# 2_MCU.net
KiCad netlist of a schematic drawn in Altium Designer
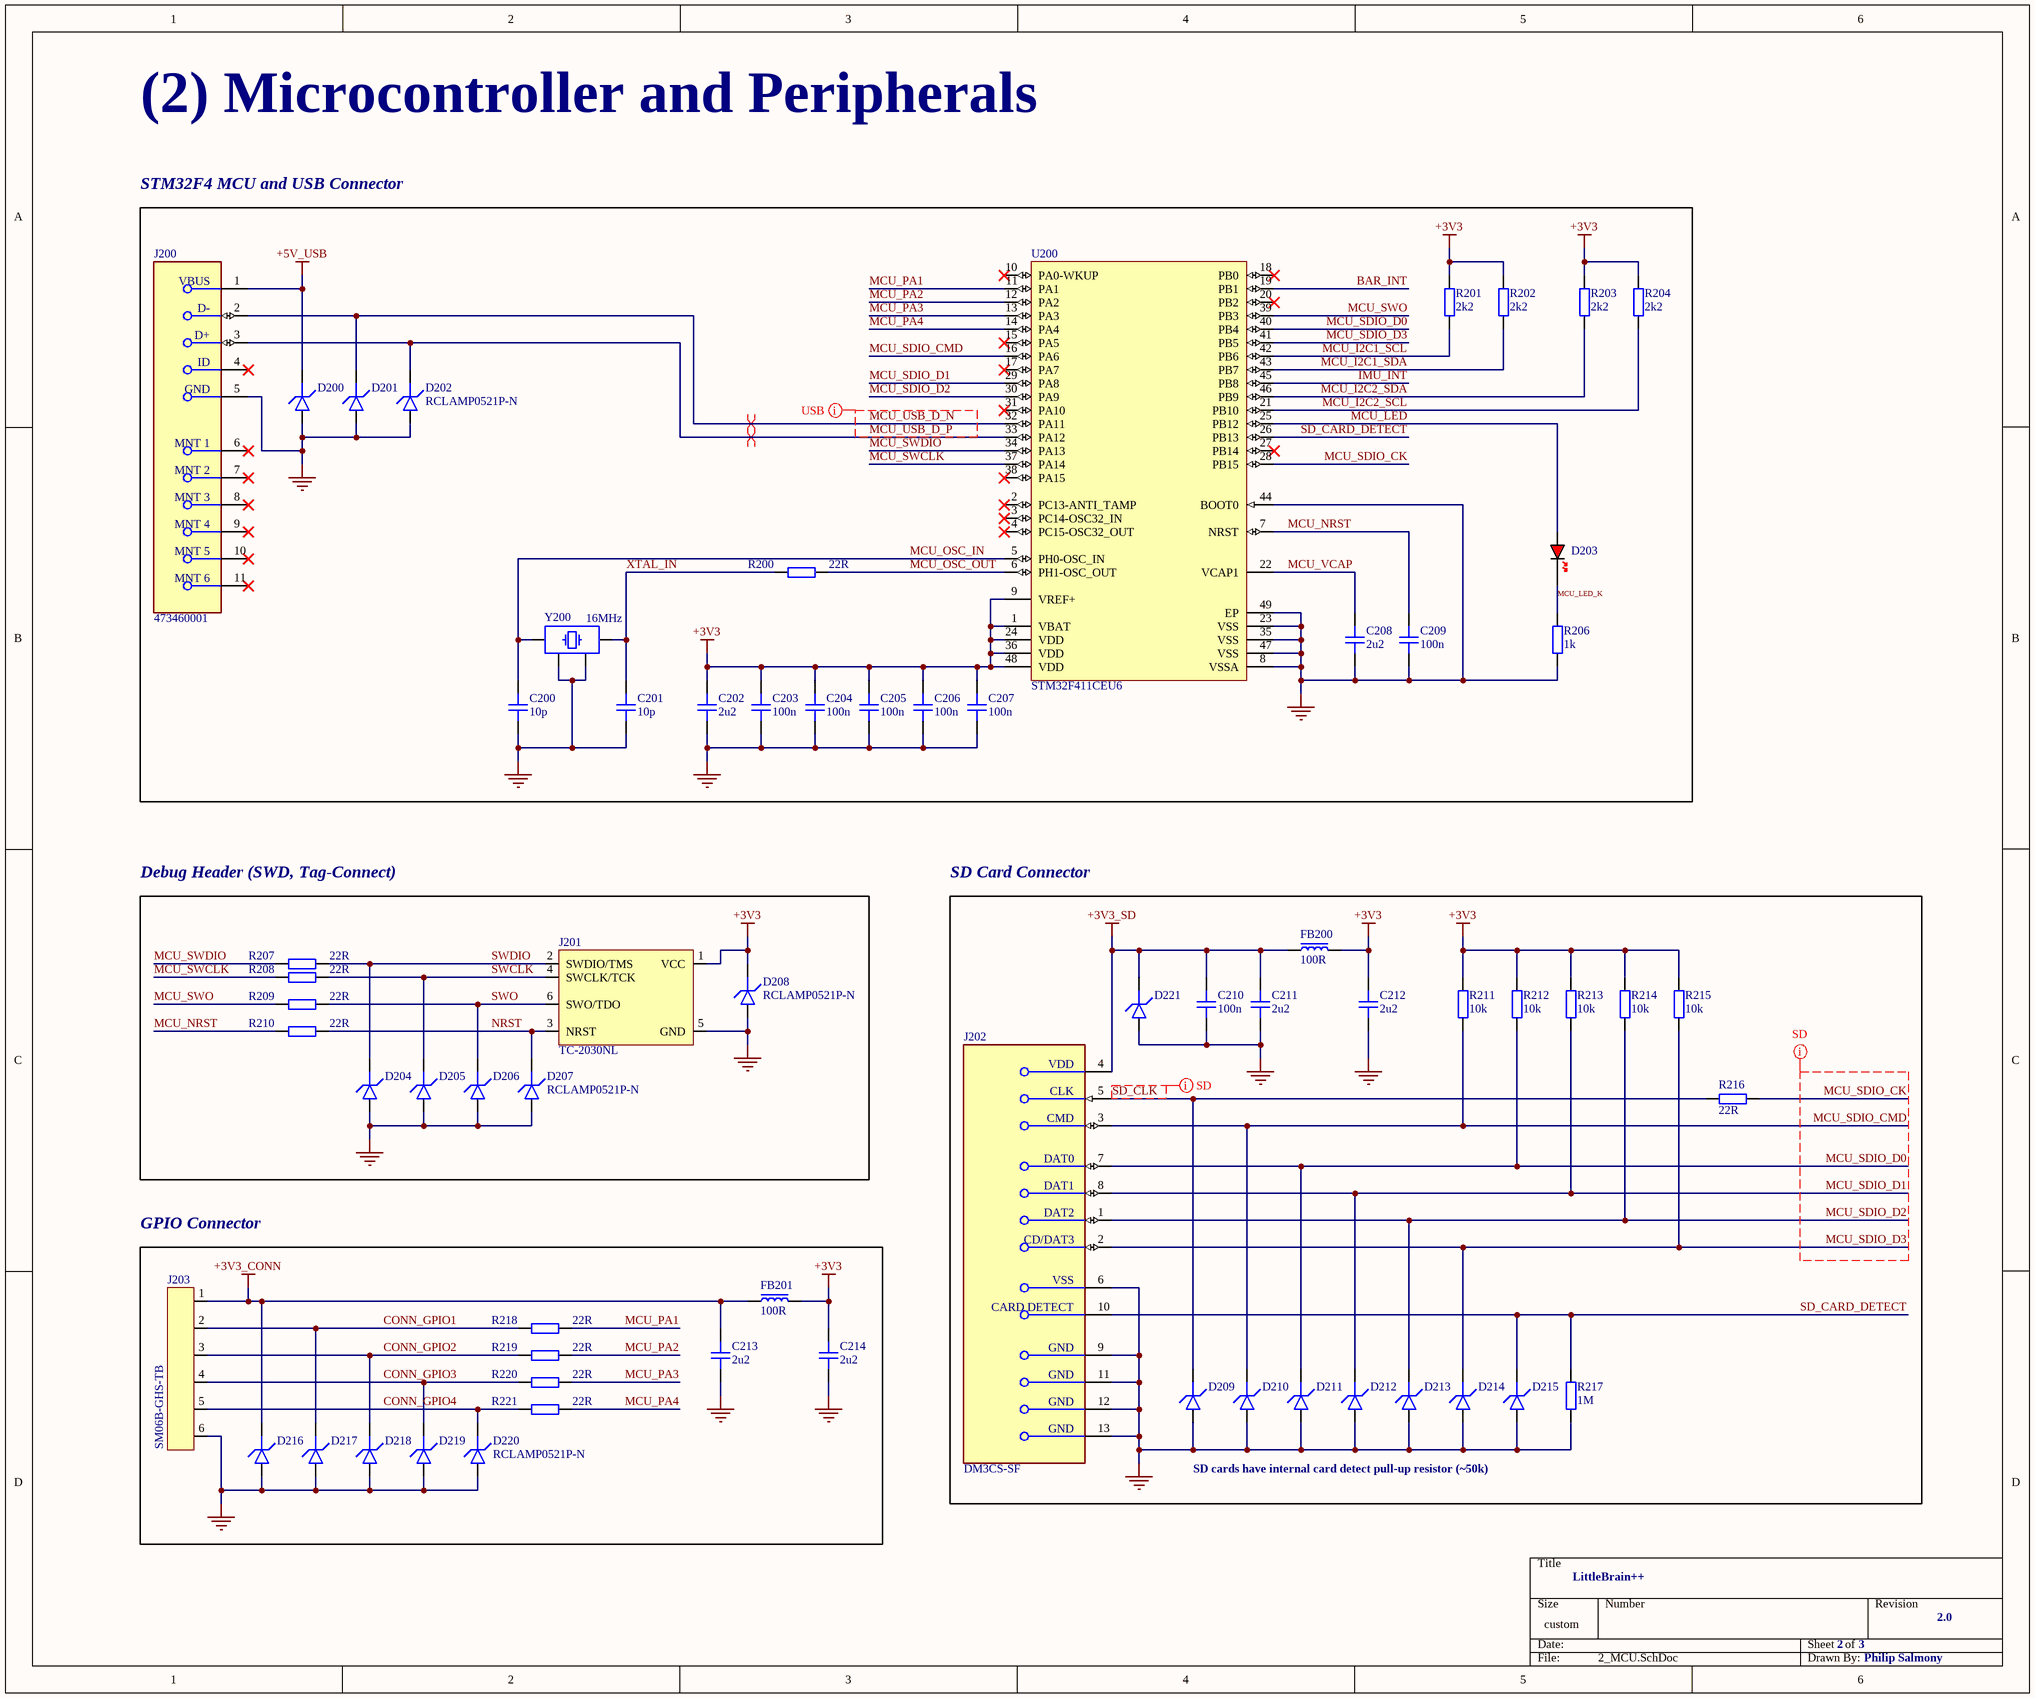
[diagram p0: 2_MCU.SchDoc]

(export (version "E")
  (design (tool "Eeschema 10.0.6"))
  (components
    (comp (ref "C200")
      (value "10p")
      (footprint "CAP_0402")
      (description "Capacitor SMD 0402 16V")
      (libsource (lib "Schematic-Lib-PhilsLab") (part "CAP_0402_16V"))
    )
    (comp (ref "C201")
      (value "10p")
      (footprint "CAP_0402")
      (description "Capacitor SMD 0402 16V")
      (libsource (lib "Schematic-Lib-PhilsLab") (part "CAP_0402_16V"))
    )
    (comp (ref "C202")
      (value "2u2")
      (footprint "CAP_0603")
      (description "Capacitor SMD 0603 16V")
      (libsource (lib "Schematic-Lib-PhilsLab") (part "CAP_0603_16V"))
    )
    (comp (ref "C203")
      (value "100n")
      (footprint "CAP_0402")
      (description "Capacitor SMD 0402 16V")
      (libsource (lib "Schematic-Lib-PhilsLab") (part "CAP_0402_16V"))
    )
    (comp (ref "C204")
      (value "100n")
      (footprint "CAP_0402")
      (description "Capacitor SMD 0402 16V")
      (libsource (lib "Schematic-Lib-PhilsLab") (part "CAP_0402_16V"))
    )
    (comp (ref "C205")
      (value "100n")
      (footprint "CAP_0402")
      (description "Capacitor SMD 0402 16V")
      (libsource (lib "Schematic-Lib-PhilsLab") (part "CAP_0402_16V"))
    )
    (comp (ref "C206")
      (value "100n")
      (footprint "CAP_0402")
      (description "Capacitor SMD 0402 16V")
      (libsource (lib "Schematic-Lib-PhilsLab") (part "CAP_0402_16V"))
    )
    (comp (ref "C207")
      (value "100n")
      (footprint "CAP_0402")
      (description "Capacitor SMD 0402 16V")
      (libsource (lib "Schematic-Lib-PhilsLab") (part "CAP_0402_16V"))
    )
    (comp (ref "C208")
      (value "2u2")
      (footprint "CAP_0603")
      (description "Capacitor SMD 0603 16V")
      (libsource (lib "Schematic-Lib-PhilsLab") (part "CAP_0603_16V"))
    )
    (comp (ref "C209")
      (value "100n")
      (footprint "CAP_0402")
      (description "Capacitor SMD 0402 16V")
      (libsource (lib "Schematic-Lib-PhilsLab") (part "CAP_0402_16V"))
    )
    (comp (ref "C210")
      (value "100n")
      (footprint "CAP_0402")
      (description "Capacitor SMD 0402 16V")
      (libsource (lib "Schematic-Lib-PhilsLab") (part "CAP_0402_16V"))
    )
    (comp (ref "C211")
      (value "2u2")
      (footprint "CAP_0603")
      (description "Capacitor SMD 0603 16V")
      (libsource (lib "Schematic-Lib-PhilsLab") (part "CAP_0603_16V"))
    )
    (comp (ref "C212")
      (value "2u2")
      (footprint "CAP_0603")
      (description "Capacitor SMD 0603 16V")
      (libsource (lib "Schematic-Lib-PhilsLab") (part "CAP_0603_16V"))
    )
    (comp (ref "C213")
      (value "2u2")
      (footprint "CAP_0603")
      (description "Capacitor SMD 0603 16V")
      (libsource (lib "Schematic-Lib-PhilsLab") (part "CAP_0603_16V"))
    )
    (comp (ref "C214")
      (value "2u2")
      (footprint "CAP_0603")
      (description "Capacitor SMD 0603 16V")
      (libsource (lib "Schematic-Lib-PhilsLab") (part "CAP_0603_16V"))
    )
    (comp (ref "D200")
      (value "RCLAMP0521P-N")
      (footprint "D_0402")
      (description "Diode TVS / ESD 0402")
      (libsource (lib "Schematic-Lib-PhilsLab") (part "D_TVS_0402"))
    )
    (comp (ref "D201")
      (value "RCLAMP0521P-N")
      (footprint "D_0402")
      (description "Diode TVS / ESD 0402")
      (libsource (lib "Schematic-Lib-PhilsLab") (part "D_TVS_0402"))
    )
    (comp (ref "D202")
      (value "RCLAMP0521P-N")
      (footprint "D_0402")
      (description "Diode TVS / ESD 0402")
      (libsource (lib "Schematic-Lib-PhilsLab") (part "D_TVS_0402"))
    )
    (comp (ref "D203")
      (value "RED")
      (footprint "LED_0402_RED")
      (description "LED 0402 RED SMD")
      (libsource (lib "Schematic-Lib-PhilsLab") (part "LED_0402_RED"))
    )
    (comp (ref "D204")
      (value "RCLAMP0521P-N")
      (footprint "D_0402")
      (description "Diode TVS / ESD 0402")
      (libsource (lib "Schematic-Lib-PhilsLab") (part "D_TVS_0402"))
    )
    (comp (ref "D205")
      (value "RCLAMP0521P-N")
      (footprint "D_0402")
      (description "Diode TVS / ESD 0402")
      (libsource (lib "Schematic-Lib-PhilsLab") (part "D_TVS_0402"))
    )
    (comp (ref "D206")
      (value "RCLAMP0521P-N")
      (footprint "D_0402")
      (description "Diode TVS / ESD 0402")
      (libsource (lib "Schematic-Lib-PhilsLab") (part "D_TVS_0402"))
    )
    (comp (ref "D207")
      (value "RCLAMP0521P-N")
      (footprint "D_0402")
      (description "Diode TVS / ESD 0402")
      (libsource (lib "Schematic-Lib-PhilsLab") (part "D_TVS_0402"))
    )
    (comp (ref "D208")
      (value "RCLAMP0521P-N")
      (footprint "D_0402")
      (description "Diode TVS / ESD 0402")
      (libsource (lib "Schematic-Lib-PhilsLab") (part "D_TVS_0402"))
    )
    (comp (ref "D209")
      (value "RCLAMP0521P-N")
      (footprint "D_0402")
      (description "Diode TVS / ESD 0402")
      (libsource (lib "Schematic-Lib-PhilsLab") (part "D_TVS_0402"))
    )
    (comp (ref "D210")
      (value "RCLAMP0521P-N")
      (footprint "D_0402")
      (description "Diode TVS / ESD 0402")
      (libsource (lib "Schematic-Lib-PhilsLab") (part "D_TVS_0402"))
    )
    (comp (ref "D211")
      (value "RCLAMP0521P-N")
      (footprint "D_0402")
      (description "Diode TVS / ESD 0402")
      (libsource (lib "Schematic-Lib-PhilsLab") (part "D_TVS_0402"))
    )
    (comp (ref "D212")
      (value "RCLAMP0521P-N")
      (footprint "D_0402")
      (description "Diode TVS / ESD 0402")
      (libsource (lib "Schematic-Lib-PhilsLab") (part "D_TVS_0402"))
    )
    (comp (ref "D213")
      (value "RCLAMP0521P-N")
      (footprint "D_0402")
      (description "Diode TVS / ESD 0402")
      (libsource (lib "Schematic-Lib-PhilsLab") (part "D_TVS_0402"))
    )
    (comp (ref "D214")
      (value "RCLAMP0521P-N")
      (footprint "D_0402")
      (description "Diode TVS / ESD 0402")
      (libsource (lib "Schematic-Lib-PhilsLab") (part "D_TVS_0402"))
    )
    (comp (ref "D215")
      (value "RCLAMP0521P-N")
      (footprint "D_0402")
      (description "Diode TVS / ESD 0402")
      (libsource (lib "Schematic-Lib-PhilsLab") (part "D_TVS_0402"))
    )
    (comp (ref "D216")
      (value "RCLAMP0521P-N")
      (footprint "D_0402")
      (description "Diode TVS / ESD 0402")
      (libsource (lib "Schematic-Lib-PhilsLab") (part "D_TVS_0402"))
    )
    (comp (ref "D217")
      (value "RCLAMP0521P-N")
      (footprint "D_0402")
      (description "Diode TVS / ESD 0402")
      (libsource (lib "Schematic-Lib-PhilsLab") (part "D_TVS_0402"))
    )
    (comp (ref "D218")
      (value "RCLAMP0521P-N")
      (footprint "D_0402")
      (description "Diode TVS / ESD 0402")
      (libsource (lib "Schematic-Lib-PhilsLab") (part "D_TVS_0402"))
    )
    (comp (ref "D219")
      (value "RCLAMP0521P-N")
      (footprint "D_0402")
      (description "Diode TVS / ESD 0402")
      (libsource (lib "Schematic-Lib-PhilsLab") (part "D_TVS_0402"))
    )
    (comp (ref "D220")
      (value "RCLAMP0521P-N")
      (footprint "D_0402")
      (description "Diode TVS / ESD 0402")
      (libsource (lib "Schematic-Lib-PhilsLab") (part "D_TVS_0402"))
    )
    (comp (ref "D221")
      (value "RCLAMP0521P-N")
      (footprint "D_0402")
      (description "Diode TVS / ESD 0402")
      (libsource (lib "Schematic-Lib-PhilsLab") (part "D_TVS_0402"))
    )
    (comp (ref "FB200")
      (value "100R")
      (footprint "FB_0603")
      (description "Ferrite Bead SMD 0603")
      (libsource (lib "Schematic-Lib-PhilsLab") (part "FB_0603"))
    )
    (comp (ref "FB201")
      (value "100R")
      (footprint "FB_0603")
      (description "Ferrite Bead SMD 0603")
      (libsource (lib "Schematic-Lib-PhilsLab") (part "FB_0603"))
    )
    (comp (ref "J200")
      (value "473460001")
      (footprint "FP-473460001-MFG")
      (description "CONN RCPT USB2.0 MICRO B SMD R/A")
      (fields
        (field (name "OCTOPART") "https://octopart.com/47346-0001-molex-7164928")
        (field (name "MANUFACTURER") "Molex")
      )
      (libsource (lib "Altium Content Vault") (part "53ae1f1d9b557310b43ca686e5bb76a"))
    )
    (comp (ref "J201")
      (value "TC-2030NL")
      (footprint "TC2030-NL-FP")
      (description "Tag-Connect No-Solder SWD Debug Connector (No Legs) DO NOT PLACE")
      (fields (field (name "MANUFACTURER") "Tag-Connect"))
      (libsource (lib "Schematic-Lib-PhilsLab") (part "TC2030-NL"))
    )
    (comp (ref "J202")
      (value "DM3CS-SF")
      (footprint "FP-DM3CS-SF-MFG")
      (description "CONN MICRO SD CARD HINGED TYPE")
      (libsource (lib "Altium Content Vault") (part "bac915de5305cfdd1ca301aae530106"))
    )
    (comp (ref "J203")
      (value "SM06B-GHS-TB")
      (footprint "SM06B-GHS-TB")
      (description "Header Connector 6 Position 1.25MM Pitch SMD Horizontal JST GH")
      (fields (field (name "MANUFACTURER") "JST"))
      (libsource (lib "Schematic-Lib-PhilsLab") (part "SM06B-GHS-TB"))
    )
    (comp (ref "R200")
      (value "22R")
      (footprint "RES_0402")
      (description "Resistor SMD 0402")
      (libsource (lib "Schematic-Lib-PhilsLab") (part "RES_0402"))
    )
    (comp (ref "R201")
      (value "2k2")
      (footprint "RES_0402")
      (description "Resistor SMD 0402")
      (libsource (lib "Schematic-Lib-PhilsLab") (part "RES_0402"))
    )
    (comp (ref "R202")
      (value "2k2")
      (footprint "RES_0402")
      (description "Resistor SMD 0402")
      (libsource (lib "Schematic-Lib-PhilsLab") (part "RES_0402"))
    )
    (comp (ref "R203")
      (value "2k2")
      (footprint "RES_0402")
      (description "Resistor SMD 0402")
      (libsource (lib "Schematic-Lib-PhilsLab") (part "RES_0402"))
    )
    (comp (ref "R204")
      (value "2k2")
      (footprint "RES_0402")
      (description "Resistor SMD 0402")
      (libsource (lib "Schematic-Lib-PhilsLab") (part "RES_0402"))
    )
    (comp (ref "R206")
      (value "1k")
      (footprint "RES_0402")
      (description "Resistor SMD 0402")
      (libsource (lib "Schematic-Lib-PhilsLab") (part "RES_0402"))
    )
    (comp (ref "R207")
      (value "22R")
      (footprint "RES_0402")
      (description "Resistor SMD 0402")
      (libsource (lib "Schematic-Lib-PhilsLab") (part "RES_0402"))
    )
    (comp (ref "R208")
      (value "22R")
      (footprint "RES_0402")
      (description "Resistor SMD 0402")
      (libsource (lib "Schematic-Lib-PhilsLab") (part "RES_0402"))
    )
    (comp (ref "R209")
      (value "22R")
      (footprint "RES_0402")
      (description "Resistor SMD 0402")
      (libsource (lib "Schematic-Lib-PhilsLab") (part "RES_0402"))
    )
    (comp (ref "R210")
      (value "22R")
      (footprint "RES_0402")
      (description "Resistor SMD 0402")
      (libsource (lib "Schematic-Lib-PhilsLab") (part "RES_0402"))
    )
    (comp (ref "R211")
      (value "10k")
      (footprint "RES_0402")
      (description "Resistor SMD 0402")
      (libsource (lib "Schematic-Lib-PhilsLab") (part "RES_0402"))
    )
    (comp (ref "R212")
      (value "10k")
      (footprint "RES_0402")
      (description "Resistor SMD 0402")
      (libsource (lib "Schematic-Lib-PhilsLab") (part "RES_0402"))
    )
    (comp (ref "R213")
      (value "10k")
      (footprint "RES_0402")
      (description "Resistor SMD 0402")
      (libsource (lib "Schematic-Lib-PhilsLab") (part "RES_0402"))
    )
    (comp (ref "R214")
      (value "10k")
      (footprint "RES_0402")
      (description "Resistor SMD 0402")
      (libsource (lib "Schematic-Lib-PhilsLab") (part "RES_0402"))
    )
    (comp (ref "R215")
      (value "10k")
      (footprint "RES_0402")
      (description "Resistor SMD 0402")
      (libsource (lib "Schematic-Lib-PhilsLab") (part "RES_0402"))
    )
    (comp (ref "R216")
      (value "22R")
      (footprint "RES_0402")
      (description "Resistor SMD 0402")
      (libsource (lib "Schematic-Lib-PhilsLab") (part "RES_0402"))
    )
    (comp (ref "R217")
      (value "1M")
      (footprint "RES_0402")
      (description "Resistor SMD 0402")
      (libsource (lib "Schematic-Lib-PhilsLab") (part "RES_0402"))
    )
    (comp (ref "R218")
      (value "22R")
      (footprint "RES_0402")
      (description "Resistor SMD 0402")
      (libsource (lib "Schematic-Lib-PhilsLab") (part "RES_0402"))
    )
    (comp (ref "R219")
      (value "22R")
      (footprint "RES_0402")
      (description "Resistor SMD 0402")
      (libsource (lib "Schematic-Lib-PhilsLab") (part "RES_0402"))
    )
    (comp (ref "R220")
      (value "22R")
      (footprint "RES_0402")
      (description "Resistor SMD 0402")
      (libsource (lib "Schematic-Lib-PhilsLab") (part "RES_0402"))
    )
    (comp (ref "R221")
      (value "22R")
      (footprint "RES_0402")
      (description "Resistor SMD 0402")
      (libsource (lib "Schematic-Lib-PhilsLab") (part "RES_0402"))
    )
    (comp (ref "U200")
      (value "STM32F411CEU6")
      (footprint "STM-UFQFPN48_L")
      (libsource (lib "Altium Content Vault") (part "MC-ARM-STM32F411-UFQFPN48"))
    )
    (comp (ref "Y200")
      (value "16MHz")
      (footprint "XTAL_3225")
      (description "Crystal SMD 24MHz 10PPM 7pF 3225")
      (fields (field (name "MANUFACTURER") "Epson"))
      (libsource (lib "Schematic-Lib-PhilsLab") (part "TSX-3225_24.0000MF15X-AC"))
    )
  )
  (nets
    (net (code "1") (name "+3V3") (class "Default")
      (node (ref "C202") (pin "2") (pinfunction "2_2") (pintype "passive"))
      (node (ref "C203") (pin "2") (pinfunction "2_2") (pintype "passive"))
      (node (ref "C204") (pin "2") (pinfunction "2_2") (pintype "passive"))
      (node (ref "C205") (pin "2") (pinfunction "2_2") (pintype "passive"))
      (node (ref "C206") (pin "2") (pinfunction "2_2") (pintype "passive"))
      (node (ref "C207") (pin "2") (pinfunction "2_2") (pintype "passive"))
      (node (ref "C212") (pin "2") (pinfunction "2_2") (pintype "passive"))
      (node (ref "C214") (pin "2") (pinfunction "2_2") (pintype "passive"))
      (node (ref "D208") (pin "K") (pinfunction "K_K") (pintype "passive"))
      (node (ref "FB200") (pin "2") (pinfunction "2_2") (pintype "passive"))
      (node (ref "FB201") (pin "2") (pinfunction "2_2") (pintype "passive"))
      (node (ref "J201") (pin "1") (pinfunction "VCC_1") (pintype "passive"))
      (node (ref "R201") (pin "2") (pinfunction "2_2") (pintype "passive"))
      (node (ref "R202") (pin "2") (pinfunction "2_2") (pintype "passive"))
      (node (ref "R203") (pin "2") (pinfunction "2_2") (pintype "passive"))
      (node (ref "R204") (pin "2") (pinfunction "2_2") (pintype "passive"))
      (node (ref "R211") (pin "2") (pinfunction "2_2") (pintype "passive"))
      (node (ref "R212") (pin "2") (pinfunction "2_2") (pintype "passive"))
      (node (ref "R213") (pin "2") (pinfunction "2_2") (pintype "passive"))
      (node (ref "R214") (pin "2") (pinfunction "2_2") (pintype "passive"))
      (node (ref "R215") (pin "2") (pinfunction "2_2") (pintype "passive"))
      (node (ref "U200") (pin "1") (pinfunction "VBAT_1") (pintype "power_in"))
      (node (ref "U200") (pin "24") (pinfunction "VDD_24") (pintype "power_in"))
      (node (ref "U200") (pin "36") (pinfunction "VDD_36") (pintype "power_in"))
      (node (ref "U200") (pin "48") (pinfunction "VDD_48") (pintype "power_in"))
      (node (ref "U200") (pin "9") (pinfunction "VREF+_9") (pintype "power_in"))
    )
    (net (code "2") (name "+3V3_CONN") (class "Default")
      (node (ref "C213") (pin "2") (pinfunction "2_2") (pintype "passive"))
      (node (ref "D216") (pin "K") (pinfunction "K_K") (pintype "passive"))
      (node (ref "FB201") (pin "1") (pinfunction "1_1") (pintype "passive"))
      (node (ref "J203") (pin "1") (pinfunction "1_1") (pintype "passive"))
    )
    (net (code "3") (name "+3V3_SD") (class "Default")
      (node (ref "C210") (pin "2") (pinfunction "2_2") (pintype "passive"))
      (node (ref "C211") (pin "2") (pinfunction "2_2") (pintype "passive"))
      (node (ref "D221") (pin "K") (pinfunction "K_K") (pintype "passive"))
      (node (ref "FB200") (pin "1") (pinfunction "1_1") (pintype "passive"))
      (node (ref "J202") (pin "4") (pinfunction "VDD_4") (pintype "power_in"))
    )
    (net (code "4") (name "+5V_USB") (class "Default")
      (node (ref "D200") (pin "K") (pinfunction "K_K") (pintype "passive"))
      (node (ref "J200") (pin "1") (pinfunction "VBUS_1") (pintype "power_in"))
    )
    (net (code "5") (name "/BAR_INT") (class "Default")
      (node (ref "U200") (pin "19") (pinfunction "PB1_19") (pintype "bidirectional"))
    )
    (net (code "6") (name "/CONN_GPIO1") (class "Default")
      (node (ref "D217") (pin "K") (pinfunction "K_K") (pintype "passive"))
      (node (ref "J203") (pin "2") (pinfunction "2_2") (pintype "passive"))
      (node (ref "R218") (pin "1") (pinfunction "1_1") (pintype "passive"))
    )
    (net (code "7") (name "/CONN_GPIO2") (class "Default")
      (node (ref "D218") (pin "K") (pinfunction "K_K") (pintype "passive"))
      (node (ref "J203") (pin "3") (pinfunction "3_3") (pintype "passive"))
      (node (ref "R219") (pin "1") (pinfunction "1_1") (pintype "passive"))
    )
    (net (code "8") (name "/CONN_GPIO3") (class "Default")
      (node (ref "D219") (pin "K") (pinfunction "K_K") (pintype "passive"))
      (node (ref "J203") (pin "4") (pinfunction "4_4") (pintype "passive"))
      (node (ref "R220") (pin "1") (pinfunction "1_1") (pintype "passive"))
    )
    (net (code "9") (name "/CONN_GPIO4") (class "Default")
      (node (ref "D220") (pin "K") (pinfunction "K_K") (pintype "passive"))
      (node (ref "J203") (pin "5") (pinfunction "5_5") (pintype "passive"))
      (node (ref "R221") (pin "1") (pinfunction "1_1") (pintype "passive"))
    )
    (net (code "10") (name "/IMU_INT") (class "Default")
      (node (ref "U200") (pin "45") (pinfunction "PB8_45") (pintype "bidirectional"))
    )
    (net (code "11") (name "/MCU_I2C1_SCL") (class "Default")
      (node (ref "R201") (pin "1") (pinfunction "1_1") (pintype "passive"))
      (node (ref "U200") (pin "42") (pinfunction "PB6_42") (pintype "bidirectional"))
    )
    (net (code "12") (name "/MCU_I2C1_SDA") (class "Default")
      (node (ref "R202") (pin "1") (pinfunction "1_1") (pintype "passive"))
      (node (ref "U200") (pin "43") (pinfunction "PB7_43") (pintype "bidirectional"))
    )
    (net (code "13") (name "/MCU_I2C2_SCL") (class "Default")
      (node (ref "R204") (pin "1") (pinfunction "1_1") (pintype "passive"))
      (node (ref "U200") (pin "21") (pinfunction "PB10_21") (pintype "bidirectional"))
    )
    (net (code "14") (name "/MCU_I2C2_SDA") (class "Default")
      (node (ref "R203") (pin "1") (pinfunction "1_1") (pintype "passive"))
      (node (ref "U200") (pin "46") (pinfunction "PB9_46") (pintype "bidirectional"))
    )
    (net (code "15") (name "/MCU_LED") (class "Default")
      (node (ref "D203") (pin "A") (pinfunction "A_A") (pintype "passive"))
      (node (ref "U200") (pin "25") (pinfunction "PB12_25") (pintype "bidirectional"))
    )
    (net (code "16") (name "/MCU_LED_K") (class "Default")
      (node (ref "D203") (pin "K") (pinfunction "K_K") (pintype "passive"))
      (node (ref "R206") (pin "2") (pinfunction "2_2") (pintype "passive"))
    )
    (net (code "17") (name "/MCU_NRST") (class "Default")
      (node (ref "C209") (pin "2") (pinfunction "2_2") (pintype "passive"))
      (node (ref "R210") (pin "1") (pinfunction "1_1") (pintype "passive"))
      (node (ref "U200") (pin "7") (pinfunction "NRST_7") (pintype "bidirectional"))
    )
    (net (code "18") (name "/MCU_OSC_IN") (class "Default")
      (node (ref "C200") (pin "2") (pinfunction "2_2") (pintype "passive"))
      (node (ref "U200") (pin "5") (pinfunction "PH0-OSC_IN_5") (pintype "bidirectional"))
      (node (ref "Y200") (pin "1") (pinfunction "1_1") (pintype "passive"))
    )
    (net (code "19") (name "/MCU_OSC_OUT") (class "Default")
      (node (ref "R200") (pin "2") (pinfunction "2_2") (pintype "passive"))
      (node (ref "U200") (pin "6") (pinfunction "PH1-OSC_OUT_6") (pintype "bidirectional"))
    )
    (net (code "20") (name "/MCU_PA1") (class "Default")
      (node (ref "R218") (pin "2") (pinfunction "2_2") (pintype "passive"))
      (node (ref "U200") (pin "11") (pinfunction "PA1_11") (pintype "bidirectional"))
    )
    (net (code "21") (name "/MCU_PA2") (class "Default")
      (node (ref "R219") (pin "2") (pinfunction "2_2") (pintype "passive"))
      (node (ref "U200") (pin "12") (pinfunction "PA2_12") (pintype "bidirectional"))
    )
    (net (code "22") (name "/MCU_PA3") (class "Default")
      (node (ref "R220") (pin "2") (pinfunction "2_2") (pintype "passive"))
      (node (ref "U200") (pin "13") (pinfunction "PA3_13") (pintype "bidirectional"))
    )
    (net (code "23") (name "/MCU_PA4") (class "Default")
      (node (ref "R221") (pin "2") (pinfunction "2_2") (pintype "passive"))
      (node (ref "U200") (pin "14") (pinfunction "PA4_14") (pintype "bidirectional"))
    )
    (net (code "24") (name "/MCU_SDIO_CK") (class "Default")
      (node (ref "R216") (pin "2") (pinfunction "2_2") (pintype "passive"))
      (node (ref "U200") (pin "28") (pinfunction "PB15_28") (pintype "bidirectional"))
    )
    (net (code "25") (name "/MCU_SDIO_CMD") (class "Default")
      (node (ref "D210") (pin "K") (pinfunction "K_K") (pintype "passive"))
      (node (ref "J202") (pin "3") (pinfunction "CMD_3") (pintype "bidirectional"))
      (node (ref "R211") (pin "1") (pinfunction "1_1") (pintype "passive"))
      (node (ref "U200") (pin "16") (pinfunction "PA6_16") (pintype "bidirectional"))
    )
    (net (code "26") (name "/MCU_SDIO_D0") (class "Default")
      (node (ref "D211") (pin "K") (pinfunction "K_K") (pintype "passive"))
      (node (ref "J202") (pin "7") (pinfunction "DAT0_7") (pintype "bidirectional"))
      (node (ref "R212") (pin "1") (pinfunction "1_1") (pintype "passive"))
      (node (ref "U200") (pin "40") (pinfunction "PB4_40") (pintype "bidirectional"))
    )
    (net (code "27") (name "/MCU_SDIO_D1") (class "Default")
      (node (ref "D212") (pin "K") (pinfunction "K_K") (pintype "passive"))
      (node (ref "J202") (pin "8") (pinfunction "DAT1_8") (pintype "bidirectional"))
      (node (ref "R213") (pin "1") (pinfunction "1_1") (pintype "passive"))
      (node (ref "U200") (pin "29") (pinfunction "PA8_29") (pintype "bidirectional"))
    )
    (net (code "28") (name "/MCU_SDIO_D2") (class "Default")
      (node (ref "D213") (pin "K") (pinfunction "K_K") (pintype "passive"))
      (node (ref "J202") (pin "1") (pinfunction "DAT2_1") (pintype "bidirectional"))
      (node (ref "R214") (pin "1") (pinfunction "1_1") (pintype "passive"))
      (node (ref "U200") (pin "30") (pinfunction "PA9_30") (pintype "bidirectional"))
    )
    (net (code "29") (name "/MCU_SDIO_D3") (class "Default")
      (node (ref "D214") (pin "K") (pinfunction "K_K") (pintype "passive"))
      (node (ref "J202") (pin "2") (pinfunction "CD/DAT3_2") (pintype "bidirectional"))
      (node (ref "R215") (pin "1") (pinfunction "1_1") (pintype "passive"))
      (node (ref "U200") (pin "41") (pinfunction "PB5_41") (pintype "bidirectional"))
    )
    (net (code "30") (name "/MCU_SWCLK") (class "Default")
      (node (ref "R208") (pin "1") (pinfunction "1_1") (pintype "passive"))
      (node (ref "U200") (pin "37") (pinfunction "PA14_37") (pintype "bidirectional"))
    )
    (net (code "31") (name "/MCU_SWDIO") (class "Default")
      (node (ref "R207") (pin "1") (pinfunction "1_1") (pintype "passive"))
      (node (ref "U200") (pin "34") (pinfunction "PA13_34") (pintype "bidirectional"))
    )
    (net (code "32") (name "/MCU_SWO") (class "Default")
      (node (ref "R209") (pin "1") (pinfunction "1_1") (pintype "passive"))
      (node (ref "U200") (pin "39") (pinfunction "PB3_39") (pintype "bidirectional"))
    )
    (net (code "33") (name "/MCU_USB_D_N") (class "Default")
      (node (ref "D201") (pin "K") (pinfunction "K_K") (pintype "passive"))
      (node (ref "J200") (pin "2") (pinfunction "D-_2") (pintype "bidirectional"))
      (node (ref "U200") (pin "32") (pinfunction "PA11_32") (pintype "bidirectional"))
    )
    (net (code "34") (name "/MCU_USB_D_P") (class "Default")
      (node (ref "D202") (pin "K") (pinfunction "K_K") (pintype "passive"))
      (node (ref "J200") (pin "3") (pinfunction "D+_3") (pintype "bidirectional"))
      (node (ref "U200") (pin "33") (pinfunction "PA12_33") (pintype "bidirectional"))
    )
    (net (code "35") (name "/MCU_VCAP") (class "Default")
      (node (ref "C208") (pin "2") (pinfunction "2_2") (pintype "passive"))
      (node (ref "U200") (pin "22") (pinfunction "VCAP1_22") (pintype "passive"))
    )
    (net (code "36") (name "/NRST") (class "Default")
      (node (ref "D207") (pin "K") (pinfunction "K_K") (pintype "passive"))
      (node (ref "J201") (pin "3") (pinfunction "NRST_3") (pintype "passive"))
      (node (ref "R210") (pin "2") (pinfunction "2_2") (pintype "passive"))
    )
    (net (code "37") (name "/SD_CARD_DETECT") (class "Default")
      (node (ref "D215") (pin "K") (pinfunction "K_K") (pintype "passive"))
      (node (ref "J202") (pin "10") (pinfunction "CARD_DETECT_10") (pintype "passive"))
      (node (ref "R217") (pin "2") (pinfunction "2_2") (pintype "passive"))
      (node (ref "U200") (pin "26") (pinfunction "PB13_26") (pintype "bidirectional"))
    )
    (net (code "38") (name "/SD_CLK") (class "Default")
      (node (ref "D209") (pin "K") (pinfunction "K_K") (pintype "passive"))
      (node (ref "J202") (pin "5") (pinfunction "CLK_5") (pintype "input"))
      (node (ref "R216") (pin "1") (pinfunction "1_1") (pintype "passive"))
    )
    (net (code "39") (name "/SWCLK") (class "Default")
      (node (ref "D205") (pin "K") (pinfunction "K_K") (pintype "passive"))
      (node (ref "J201") (pin "4") (pinfunction "SWCLK/TCK_4") (pintype "passive"))
      (node (ref "R208") (pin "2") (pinfunction "2_2") (pintype "passive"))
    )
    (net (code "40") (name "/SWDIO") (class "Default")
      (node (ref "D204") (pin "K") (pinfunction "K_K") (pintype "passive"))
      (node (ref "J201") (pin "2") (pinfunction "SWDIO/TMS_2") (pintype "passive"))
      (node (ref "R207") (pin "2") (pinfunction "2_2") (pintype "passive"))
    )
    (net (code "41") (name "/SWO") (class "Default")
      (node (ref "D206") (pin "K") (pinfunction "K_K") (pintype "passive"))
      (node (ref "J201") (pin "6") (pinfunction "SWO/TDO_6") (pintype "passive"))
      (node (ref "R209") (pin "2") (pinfunction "2_2") (pintype "passive"))
    )
    (net (code "42") (name "/XTAL_IN") (class "Default")
      (node (ref "C201") (pin "2") (pinfunction "2_2") (pintype "passive"))
      (node (ref "R200") (pin "1") (pinfunction "1_1") (pintype "passive"))
      (node (ref "Y200") (pin "3") (pinfunction "3_3") (pintype "passive"))
    )
    (net (code "43") (name "GND") (class "Default")
      (node (ref "C200") (pin "1") (pinfunction "1_1") (pintype "passive"))
      (node (ref "C201") (pin "1") (pinfunction "1_1") (pintype "passive"))
      (node (ref "C202") (pin "1") (pinfunction "1_1") (pintype "passive"))
      (node (ref "C203") (pin "1") (pinfunction "1_1") (pintype "passive"))
      (node (ref "C204") (pin "1") (pinfunction "1_1") (pintype "passive"))
      (node (ref "C205") (pin "1") (pinfunction "1_1") (pintype "passive"))
      (node (ref "C206") (pin "1") (pinfunction "1_1") (pintype "passive"))
      (node (ref "C207") (pin "1") (pinfunction "1_1") (pintype "passive"))
      (node (ref "C208") (pin "1") (pinfunction "1_1") (pintype "passive"))
      (node (ref "C209") (pin "1") (pinfunction "1_1") (pintype "passive"))
      (node (ref "C210") (pin "1") (pinfunction "1_1") (pintype "passive"))
      (node (ref "C211") (pin "1") (pinfunction "1_1") (pintype "passive"))
      (node (ref "C212") (pin "1") (pinfunction "1_1") (pintype "passive"))
      (node (ref "C213") (pin "1") (pinfunction "1_1") (pintype "passive"))
      (node (ref "C214") (pin "1") (pinfunction "1_1") (pintype "passive"))
      (node (ref "D200") (pin "A") (pinfunction "A_A") (pintype "passive"))
      (node (ref "D201") (pin "A") (pinfunction "A_A") (pintype "passive"))
      (node (ref "D202") (pin "A") (pinfunction "A_A") (pintype "passive"))
      (node (ref "D204") (pin "A") (pinfunction "A_A") (pintype "passive"))
      (node (ref "D205") (pin "A") (pinfunction "A_A") (pintype "passive"))
      (node (ref "D206") (pin "A") (pinfunction "A_A") (pintype "passive"))
      (node (ref "D207") (pin "A") (pinfunction "A_A") (pintype "passive"))
      (node (ref "D208") (pin "A") (pinfunction "A_A") (pintype "passive"))
      (node (ref "D209") (pin "A") (pinfunction "A_A") (pintype "passive"))
      (node (ref "D210") (pin "A") (pinfunction "A_A") (pintype "passive"))
      (node (ref "D211") (pin "A") (pinfunction "A_A") (pintype "passive"))
      (node (ref "D212") (pin "A") (pinfunction "A_A") (pintype "passive"))
      (node (ref "D213") (pin "A") (pinfunction "A_A") (pintype "passive"))
      (node (ref "D214") (pin "A") (pinfunction "A_A") (pintype "passive"))
      (node (ref "D215") (pin "A") (pinfunction "A_A") (pintype "passive"))
      (node (ref "D216") (pin "A") (pinfunction "A_A") (pintype "passive"))
      (node (ref "D217") (pin "A") (pinfunction "A_A") (pintype "passive"))
      (node (ref "D218") (pin "A") (pinfunction "A_A") (pintype "passive"))
      (node (ref "D219") (pin "A") (pinfunction "A_A") (pintype "passive"))
      (node (ref "D220") (pin "A") (pinfunction "A_A") (pintype "passive"))
      (node (ref "D221") (pin "A") (pinfunction "A_A") (pintype "passive"))
      (node (ref "J200") (pin "5") (pinfunction "GND_5") (pintype "power_in"))
      (node (ref "J201") (pin "5") (pinfunction "GND_5") (pintype "passive"))
      (node (ref "J202") (pin "11") (pinfunction "GND_11") (pintype "power_in"))
      (node (ref "J202") (pin "12") (pinfunction "GND_12") (pintype "power_in"))
      (node (ref "J202") (pin "13") (pinfunction "GND_13") (pintype "power_in"))
      (node (ref "J202") (pin "6") (pinfunction "VSS_6") (pintype "power_in"))
      (node (ref "J202") (pin "9") (pinfunction "GND_9") (pintype "power_in"))
      (node (ref "J203") (pin "6") (pinfunction "6_6") (pintype "passive"))
      (node (ref "R206") (pin "1") (pinfunction "1_1") (pintype "passive"))
      (node (ref "R217") (pin "1") (pinfunction "1_1") (pintype "passive"))
      (node (ref "U200") (pin "23") (pinfunction "VSS_23") (pintype "power_in"))
      (node (ref "U200") (pin "35") (pinfunction "VSS_35") (pintype "power_in"))
      (node (ref "U200") (pin "44") (pinfunction "BOOT0_44") (pintype "input"))
      (node (ref "U200") (pin "47") (pinfunction "VSS_47") (pintype "power_in"))
      (node (ref "U200") (pin "49") (pinfunction "EP_49") (pintype "power_in"))
      (node (ref "U200") (pin "8") (pinfunction "VSSA_8") (pintype "power_in"))
      (node (ref "Y200") (pin "2") (pinfunction "2_2") (pintype "passive"))
      (node (ref "Y200") (pin "4") (pinfunction "4_4") (pintype "passive"))
    )
    (net (code "44") (name "unconnected-(J200-ID-Pad4)") (class "Default")
      (node (ref "J200") (pin "4") (pinfunction "ID_4") (pintype "passive+no_connect"))
    )
    (net (code "45") (name "unconnected-(J200-MNT_1-Pad6)") (class "Default")
      (node (ref "J200") (pin "6") (pinfunction "MNT_1_6") (pintype "passive+no_connect"))
    )
    (net (code "46") (name "unconnected-(J200-MNT_2-Pad7)") (class "Default")
      (node (ref "J200") (pin "7") (pinfunction "MNT_2_7") (pintype "passive+no_connect"))
    )
    (net (code "47") (name "unconnected-(J200-MNT_3-Pad8)") (class "Default")
      (node (ref "J200") (pin "8") (pinfunction "MNT_3_8") (pintype "passive+no_connect"))
    )
    (net (code "48") (name "unconnected-(J200-MNT_4-Pad9)") (class "Default")
      (node (ref "J200") (pin "9") (pinfunction "MNT_4_9") (pintype "passive+no_connect"))
    )
    (net (code "49") (name "unconnected-(J200-MNT_5-Pad10)") (class "Default")
      (node (ref "J200") (pin "10") (pinfunction "MNT_5_10") (pintype "passive+no_connect"))
    )
    (net (code "50") (name "unconnected-(J200-MNT_6-Pad11)") (class "Default")
      (node (ref "J200") (pin "11") (pinfunction "MNT_6_11") (pintype "passive+no_connect"))
    )
    (net (code "51") (name "unconnected-(U200-PA0-WKUP-Pad10)") (class "Default")
      (node (ref "U200") (pin "10") (pinfunction "PA0-WKUP_10") (pintype "bidirectional+no_connect"))
    )
    (net (code "52") (name "unconnected-(U200-PA5-Pad15)") (class "Default")
      (node (ref "U200") (pin "15") (pinfunction "PA5_15") (pintype "bidirectional+no_connect"))
    )
    (net (code "53") (name "unconnected-(U200-PA7-Pad17)") (class "Default")
      (node (ref "U200") (pin "17") (pinfunction "PA7_17") (pintype "bidirectional+no_connect"))
    )
    (net (code "54") (name "unconnected-(U200-PA10-Pad31)") (class "Default")
      (node (ref "U200") (pin "31") (pinfunction "PA10_31") (pintype "bidirectional+no_connect"))
    )
    (net (code "55") (name "unconnected-(U200-PA15-Pad38)") (class "Default")
      (node (ref "U200") (pin "38") (pinfunction "PA15_38") (pintype "bidirectional+no_connect"))
    )
    (net (code "56") (name "unconnected-(U200-PB0-Pad18)") (class "Default")
      (node (ref "U200") (pin "18") (pinfunction "PB0_18") (pintype "bidirectional+no_connect"))
    )
    (net (code "57") (name "unconnected-(U200-PB2-Pad20)") (class "Default")
      (node (ref "U200") (pin "20") (pinfunction "PB2_20") (pintype "bidirectional+no_connect"))
    )
    (net (code "58") (name "unconnected-(U200-PB14-Pad27)") (class "Default")
      (node (ref "U200") (pin "27") (pinfunction "PB14_27") (pintype "bidirectional+no_connect"))
    )
    (net (code "59") (name "unconnected-(U200-PC13-ANTI_TAMP-Pad2)") (class "Default")
      (node (ref "U200") (pin "2") (pinfunction "PC13-ANTI_TAMP_2") (pintype "bidirectional+no_connect"))
    )
    (net (code "60") (name "unconnected-(U200-PC14-OSC32_IN-Pad3)") (class "Default")
      (node (ref "U200") (pin "3") (pinfunction "PC14-OSC32_IN_3") (pintype "bidirectional+no_connect"))
    )
    (net (code "61") (name "unconnected-(U200-PC15-OSC32_OUT-Pad4)") (class "Default")
      (node (ref "U200") (pin "4") (pinfunction "PC15-OSC32_OUT_4") (pintype "bidirectional+no_connect"))
    )
  )
)
